# LED_Control_A0-A3.net
KiCad netlist of a schematic drawn in Altium Designer
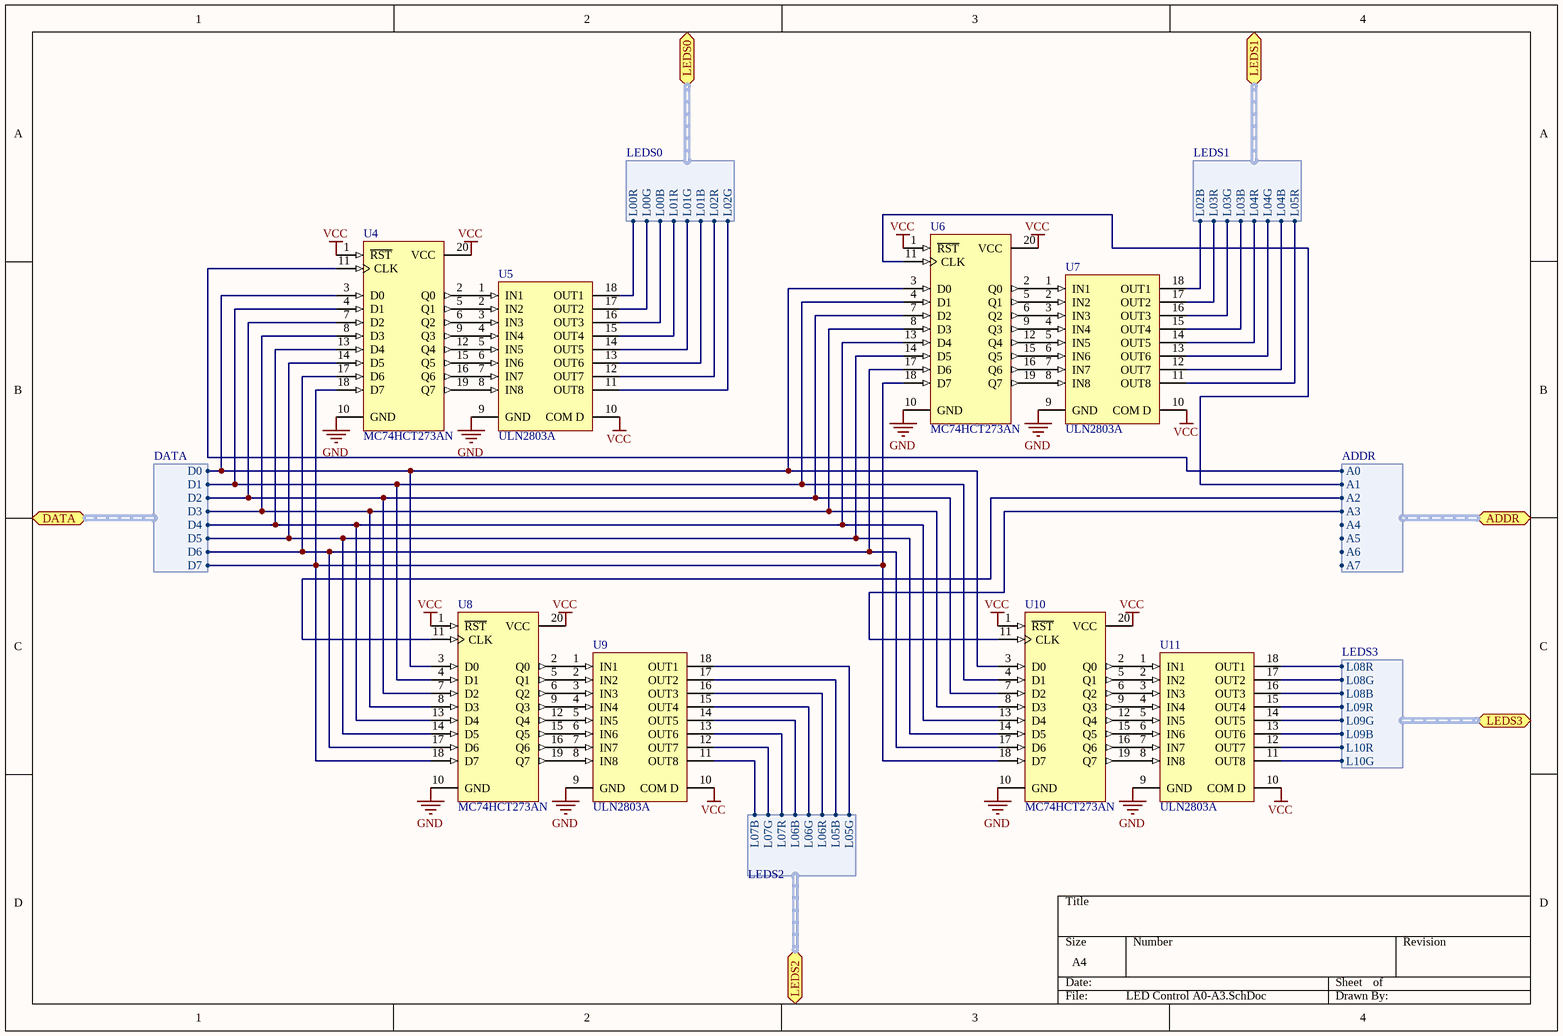
[diagram p0: LED Control A0-A3.SchDoc]

(export (version "E")
  (design (tool "Eeschema 10.0.6"))
  (components
    (comp (ref "U4")
      (value "MC74HCT273AN")
      (footprint "738-03")
      (description "Octal D-Type Flip-Flop with Common Clock and Reset with LSTTL-Compatible Inputs")
      (fields (field (name "PUBLISHER") "Altium Limited"))
      (libsource (lib "ON Semi Logic Flip-Flop") (part "MC74HCT273AN"))
    )
    (comp (ref "U5")
      (value "ULN2803A")
      (footprint "DIP18")
      (description "Eight Darlington Array")
      (fields (field (name "PUBLISHER") "Altium Limited"))
      (libsource (lib "ST Interface Darlington Driver") (part "ULN2803A"))
    )
    (comp (ref "U6")
      (value "MC74HCT273AN")
      (footprint "738-03")
      (description "Octal D-Type Flip-Flop with Common Clock and Reset with LSTTL-Compatible Inputs")
      (fields (field (name "PUBLISHER") "Altium Limited"))
      (libsource (lib "ON Semi Logic Flip-Flop") (part "MC74HCT273AN"))
    )
    (comp (ref "U7")
      (value "ULN2803A")
      (footprint "DIP18")
      (description "Eight Darlington Array")
      (fields (field (name "PUBLISHER") "Altium Limited"))
      (libsource (lib "ST Interface Darlington Driver") (part "ULN2803A"))
    )
    (comp (ref "U8")
      (value "MC74HCT273AN")
      (footprint "738-03")
      (description "Octal D-Type Flip-Flop with Common Clock and Reset with LSTTL-Compatible Inputs")
      (fields (field (name "PUBLISHER") "Altium Limited"))
      (libsource (lib "ON Semi Logic Flip-Flop") (part "MC74HCT273AN"))
    )
    (comp (ref "U9")
      (value "ULN2803A")
      (footprint "DIP18")
      (description "Eight Darlington Array")
      (fields (field (name "PUBLISHER") "Altium Limited"))
      (libsource (lib "ST Interface Darlington Driver") (part "ULN2803A"))
    )
    (comp (ref "U10")
      (value "MC74HCT273AN")
      (footprint "738-03")
      (description "Octal D-Type Flip-Flop with Common Clock and Reset with LSTTL-Compatible Inputs")
      (fields (field (name "PUBLISHER") "Altium Limited"))
      (libsource (lib "ON Semi Logic Flip-Flop") (part "MC74HCT273AN"))
    )
    (comp (ref "U11")
      (value "ULN2803A")
      (footprint "DIP18")
      (description "Eight Darlington Array")
      (fields (field (name "PUBLISHER") "Altium Limited"))
      (libsource (lib "ST Interface Darlington Driver") (part "ULN2803A"))
    )
  )
  (nets
    (net (code "7") (name "/A0") (class "Default")
      (node (ref "U4") (pin "11") (pinfunction "CLK_11") (pintype "input"))
    )
    (net (code "8") (name "/A1") (class "Default")
      (node (ref "U6") (pin "11") (pinfunction "CLK_11") (pintype "input"))
    )
    (net (code "9") (name "/A2") (class "Default")
      (node (ref "U8") (pin "11") (pinfunction "CLK_11") (pintype "input"))
    )
    (net (code "10") (name "/A3") (class "Default")
      (node (ref "U10") (pin "11") (pinfunction "CLK_11") (pintype "input"))
    )
    (net (code "11") (name "/D0") (class "Default")
      (node (ref "U10") (pin "3") (pinfunction "D0_3") (pintype "input"))
      (node (ref "U4") (pin "3") (pinfunction "D0_3") (pintype "input"))
      (node (ref "U6") (pin "3") (pinfunction "D0_3") (pintype "input"))
      (node (ref "U8") (pin "3") (pinfunction "D0_3") (pintype "input"))
    )
    (net (code "12") (name "/D1") (class "Default")
      (node (ref "U10") (pin "4") (pinfunction "D1_4") (pintype "input"))
      (node (ref "U4") (pin "4") (pinfunction "D1_4") (pintype "input"))
      (node (ref "U6") (pin "4") (pinfunction "D1_4") (pintype "input"))
      (node (ref "U8") (pin "4") (pinfunction "D1_4") (pintype "input"))
    )
    (net (code "13") (name "/D2") (class "Default")
      (node (ref "U10") (pin "7") (pinfunction "D2_7") (pintype "input"))
      (node (ref "U4") (pin "7") (pinfunction "D2_7") (pintype "input"))
      (node (ref "U6") (pin "7") (pinfunction "D2_7") (pintype "input"))
      (node (ref "U8") (pin "7") (pinfunction "D2_7") (pintype "input"))
    )
    (net (code "14") (name "/D3") (class "Default")
      (node (ref "U10") (pin "8") (pinfunction "D3_8") (pintype "input"))
      (node (ref "U4") (pin "8") (pinfunction "D3_8") (pintype "input"))
      (node (ref "U6") (pin "8") (pinfunction "D3_8") (pintype "input"))
      (node (ref "U8") (pin "8") (pinfunction "D3_8") (pintype "input"))
    )
    (net (code "15") (name "/D4") (class "Default")
      (node (ref "U10") (pin "13") (pinfunction "D4_13") (pintype "input"))
      (node (ref "U4") (pin "13") (pinfunction "D4_13") (pintype "input"))
      (node (ref "U6") (pin "13") (pinfunction "D4_13") (pintype "input"))
      (node (ref "U8") (pin "13") (pinfunction "D4_13") (pintype "input"))
    )
    (net (code "16") (name "/D5") (class "Default")
      (node (ref "U10") (pin "14") (pinfunction "D5_14") (pintype "input"))
      (node (ref "U4") (pin "14") (pinfunction "D5_14") (pintype "input"))
      (node (ref "U6") (pin "14") (pinfunction "D5_14") (pintype "input"))
      (node (ref "U8") (pin "14") (pinfunction "D5_14") (pintype "input"))
    )
    (net (code "17") (name "/D6") (class "Default")
      (node (ref "U10") (pin "17") (pinfunction "D6_17") (pintype "input"))
      (node (ref "U4") (pin "17") (pinfunction "D6_17") (pintype "input"))
      (node (ref "U6") (pin "17") (pinfunction "D6_17") (pintype "input"))
      (node (ref "U8") (pin "17") (pinfunction "D6_17") (pintype "input"))
    )
    (net (code "18") (name "/D7") (class "Default")
      (node (ref "U10") (pin "18") (pinfunction "D7_18") (pintype "input"))
      (node (ref "U4") (pin "18") (pinfunction "D7_18") (pintype "input"))
      (node (ref "U6") (pin "18") (pinfunction "D7_18") (pintype "input"))
      (node (ref "U8") (pin "18") (pinfunction "D7_18") (pintype "input"))
    )
    (net (code "19") (name "/L00B") (class "Default")
      (node (ref "U5") (pin "16") (pinfunction "OUT3_16") (pintype "open_collector"))
    )
    (net (code "20") (name "/L00G") (class "Default")
      (node (ref "U5") (pin "17") (pinfunction "OUT2_17") (pintype "open_collector"))
    )
    (net (code "21") (name "/L00R") (class "Default")
      (node (ref "U5") (pin "18") (pinfunction "OUT1_18") (pintype "open_collector"))
    )
    (net (code "22") (name "/L01B") (class "Default")
      (node (ref "U5") (pin "13") (pinfunction "OUT6_13") (pintype "open_collector"))
    )
    (net (code "23") (name "/L01G") (class "Default")
      (node (ref "U5") (pin "14") (pinfunction "OUT5_14") (pintype "open_collector"))
    )
    (net (code "24") (name "/L01R") (class "Default")
      (node (ref "U5") (pin "15") (pinfunction "OUT4_15") (pintype "open_collector"))
    )
    (net (code "25") (name "/L02B") (class "Default")
      (node (ref "U7") (pin "18") (pinfunction "OUT1_18") (pintype "open_collector"))
    )
    (net (code "26") (name "/L02G") (class "Default")
      (node (ref "U5") (pin "11") (pinfunction "OUT8_11") (pintype "open_collector"))
    )
    (net (code "27") (name "/L02R") (class "Default")
      (node (ref "U5") (pin "12") (pinfunction "OUT7_12") (pintype "open_collector"))
    )
    (net (code "28") (name "/L03B") (class "Default")
      (node (ref "U7") (pin "15") (pinfunction "OUT4_15") (pintype "open_collector"))
    )
    (net (code "29") (name "/L03G") (class "Default")
      (node (ref "U7") (pin "16") (pinfunction "OUT3_16") (pintype "open_collector"))
    )
    (net (code "30") (name "/L03R") (class "Default")
      (node (ref "U7") (pin "17") (pinfunction "OUT2_17") (pintype "open_collector"))
    )
    (net (code "31") (name "/L04B") (class "Default")
      (node (ref "U7") (pin "12") (pinfunction "OUT7_12") (pintype "open_collector"))
    )
    (net (code "32") (name "/L04G") (class "Default")
      (node (ref "U7") (pin "13") (pinfunction "OUT6_13") (pintype "open_collector"))
    )
    (net (code "33") (name "/L04R") (class "Default")
      (node (ref "U7") (pin "14") (pinfunction "OUT5_14") (pintype "open_collector"))
    )
    (net (code "34") (name "/L05B") (class "Default")
      (node (ref "U9") (pin "17") (pinfunction "OUT2_17") (pintype "open_collector"))
    )
    (net (code "35") (name "/L05G") (class "Default")
      (node (ref "U9") (pin "18") (pinfunction "OUT1_18") (pintype "open_collector"))
    )
    (net (code "36") (name "/L05R") (class "Default")
      (node (ref "U7") (pin "11") (pinfunction "OUT8_11") (pintype "open_collector"))
    )
    (net (code "37") (name "/L06B") (class "Default")
      (node (ref "U9") (pin "14") (pinfunction "OUT5_14") (pintype "open_collector"))
    )
    (net (code "38") (name "/L06G") (class "Default")
      (node (ref "U9") (pin "15") (pinfunction "OUT4_15") (pintype "open_collector"))
    )
    (net (code "39") (name "/L06R") (class "Default")
      (node (ref "U9") (pin "16") (pinfunction "OUT3_16") (pintype "open_collector"))
    )
    (net (code "40") (name "/L07B") (class "Default")
      (node (ref "U9") (pin "11") (pinfunction "OUT8_11") (pintype "open_collector"))
    )
    (net (code "41") (name "/L07G") (class "Default")
      (node (ref "U9") (pin "12") (pinfunction "OUT7_12") (pintype "open_collector"))
    )
    (net (code "42") (name "/L07R") (class "Default")
      (node (ref "U9") (pin "13") (pinfunction "OUT6_13") (pintype "open_collector"))
    )
    (net (code "43") (name "/L08B") (class "Default")
      (node (ref "U11") (pin "16") (pinfunction "OUT3_16") (pintype "open_collector"))
    )
    (net (code "44") (name "/L08G") (class "Default")
      (node (ref "U11") (pin "17") (pinfunction "OUT2_17") (pintype "open_collector"))
    )
    (net (code "45") (name "/L08R") (class "Default")
      (node (ref "U11") (pin "18") (pinfunction "OUT1_18") (pintype "open_collector"))
    )
    (net (code "46") (name "/L09B") (class "Default")
      (node (ref "U11") (pin "13") (pinfunction "OUT6_13") (pintype "open_collector"))
    )
    (net (code "47") (name "/L09G") (class "Default")
      (node (ref "U11") (pin "14") (pinfunction "OUT5_14") (pintype "open_collector"))
    )
    (net (code "48") (name "/L09R") (class "Default")
      (node (ref "U11") (pin "15") (pinfunction "OUT4_15") (pintype "open_collector"))
    )
    (net (code "49") (name "/L10G") (class "Default")
      (node (ref "U11") (pin "11") (pinfunction "OUT8_11") (pintype "open_collector"))
    )
    (net (code "50") (name "/L10R") (class "Default")
      (node (ref "U11") (pin "12") (pinfunction "OUT7_12") (pintype "open_collector"))
    )
    (net (code "57") (name "GND") (class "Default")
      (node (ref "U10") (pin "10") (pinfunction "GND_10") (pintype "power_in"))
      (node (ref "U11") (pin "9") (pinfunction "GND_9") (pintype "power_in"))
      (node (ref "U4") (pin "10") (pinfunction "GND_10") (pintype "power_in"))
      (node (ref "U5") (pin "9") (pinfunction "GND_9") (pintype "power_in"))
      (node (ref "U6") (pin "10") (pinfunction "GND_10") (pintype "power_in"))
      (node (ref "U7") (pin "9") (pinfunction "GND_9") (pintype "power_in"))
      (node (ref "U8") (pin "10") (pinfunction "GND_10") (pintype "power_in"))
      (node (ref "U9") (pin "9") (pinfunction "GND_9") (pintype "power_in"))
    )
    (net (code "58") (name "Net-(U4-Q0)") (class "Default")
      (node (ref "U4") (pin "2") (pinfunction "Q0_2") (pintype "output"))
      (node (ref "U5") (pin "1") (pinfunction "IN1_1") (pintype "input"))
    )
    (net (code "59") (name "Net-(U4-Q1)") (class "Default")
      (node (ref "U4") (pin "5") (pinfunction "Q1_5") (pintype "output"))
      (node (ref "U5") (pin "2") (pinfunction "IN2_2") (pintype "input"))
    )
    (net (code "60") (name "Net-(U4-Q2)") (class "Default")
      (node (ref "U4") (pin "6") (pinfunction "Q2_6") (pintype "output"))
      (node (ref "U5") (pin "3") (pinfunction "IN3_3") (pintype "input"))
    )
    (net (code "61") (name "Net-(U4-Q3)") (class "Default")
      (node (ref "U4") (pin "9") (pinfunction "Q3_9") (pintype "output"))
      (node (ref "U5") (pin "4") (pinfunction "IN4_4") (pintype "input"))
    )
    (net (code "62") (name "Net-(U4-Q4)") (class "Default")
      (node (ref "U4") (pin "12") (pinfunction "Q4_12") (pintype "output"))
      (node (ref "U5") (pin "5") (pinfunction "IN5_5") (pintype "input"))
    )
    (net (code "63") (name "Net-(U4-Q5)") (class "Default")
      (node (ref "U4") (pin "15") (pinfunction "Q5_15") (pintype "output"))
      (node (ref "U5") (pin "6") (pinfunction "IN6_6") (pintype "input"))
    )
    (net (code "64") (name "Net-(U4-Q6)") (class "Default")
      (node (ref "U4") (pin "16") (pinfunction "Q6_16") (pintype "output"))
      (node (ref "U5") (pin "7") (pinfunction "IN7_7") (pintype "input"))
    )
    (net (code "65") (name "Net-(U4-Q7)") (class "Default")
      (node (ref "U4") (pin "19") (pinfunction "Q7_19") (pintype "output"))
      (node (ref "U5") (pin "8") (pinfunction "IN8_8") (pintype "input"))
    )
    (net (code "66") (name "Net-(U6-Q0)") (class "Default")
      (node (ref "U6") (pin "2") (pinfunction "Q0_2") (pintype "output"))
      (node (ref "U7") (pin "1") (pinfunction "IN1_1") (pintype "input"))
    )
    (net (code "67") (name "Net-(U6-Q1)") (class "Default")
      (node (ref "U6") (pin "5") (pinfunction "Q1_5") (pintype "output"))
      (node (ref "U7") (pin "2") (pinfunction "IN2_2") (pintype "input"))
    )
    (net (code "68") (name "Net-(U6-Q2)") (class "Default")
      (node (ref "U6") (pin "6") (pinfunction "Q2_6") (pintype "output"))
      (node (ref "U7") (pin "3") (pinfunction "IN3_3") (pintype "input"))
    )
    (net (code "69") (name "Net-(U6-Q3)") (class "Default")
      (node (ref "U6") (pin "9") (pinfunction "Q3_9") (pintype "output"))
      (node (ref "U7") (pin "4") (pinfunction "IN4_4") (pintype "input"))
    )
    (net (code "70") (name "Net-(U6-Q4)") (class "Default")
      (node (ref "U6") (pin "12") (pinfunction "Q4_12") (pintype "output"))
      (node (ref "U7") (pin "5") (pinfunction "IN5_5") (pintype "input"))
    )
    (net (code "71") (name "Net-(U6-Q5)") (class "Default")
      (node (ref "U6") (pin "15") (pinfunction "Q5_15") (pintype "output"))
      (node (ref "U7") (pin "6") (pinfunction "IN6_6") (pintype "input"))
    )
    (net (code "72") (name "Net-(U6-Q6)") (class "Default")
      (node (ref "U6") (pin "16") (pinfunction "Q6_16") (pintype "output"))
      (node (ref "U7") (pin "7") (pinfunction "IN7_7") (pintype "input"))
    )
    (net (code "73") (name "Net-(U6-Q7)") (class "Default")
      (node (ref "U6") (pin "19") (pinfunction "Q7_19") (pintype "output"))
      (node (ref "U7") (pin "8") (pinfunction "IN8_8") (pintype "input"))
    )
    (net (code "74") (name "Net-(U8-Q0)") (class "Default")
      (node (ref "U8") (pin "2") (pinfunction "Q0_2") (pintype "output"))
      (node (ref "U9") (pin "1") (pinfunction "IN1_1") (pintype "input"))
    )
    (net (code "75") (name "Net-(U8-Q1)") (class "Default")
      (node (ref "U8") (pin "5") (pinfunction "Q1_5") (pintype "output"))
      (node (ref "U9") (pin "2") (pinfunction "IN2_2") (pintype "input"))
    )
    (net (code "76") (name "Net-(U8-Q2)") (class "Default")
      (node (ref "U8") (pin "6") (pinfunction "Q2_6") (pintype "output"))
      (node (ref "U9") (pin "3") (pinfunction "IN3_3") (pintype "input"))
    )
    (net (code "77") (name "Net-(U8-Q3)") (class "Default")
      (node (ref "U8") (pin "9") (pinfunction "Q3_9") (pintype "output"))
      (node (ref "U9") (pin "4") (pinfunction "IN4_4") (pintype "input"))
    )
    (net (code "78") (name "Net-(U8-Q4)") (class "Default")
      (node (ref "U8") (pin "12") (pinfunction "Q4_12") (pintype "output"))
      (node (ref "U9") (pin "5") (pinfunction "IN5_5") (pintype "input"))
    )
    (net (code "79") (name "Net-(U8-Q5)") (class "Default")
      (node (ref "U8") (pin "15") (pinfunction "Q5_15") (pintype "output"))
      (node (ref "U9") (pin "6") (pinfunction "IN6_6") (pintype "input"))
    )
    (net (code "80") (name "Net-(U8-Q6)") (class "Default")
      (node (ref "U8") (pin "16") (pinfunction "Q6_16") (pintype "output"))
      (node (ref "U9") (pin "7") (pinfunction "IN7_7") (pintype "input"))
    )
    (net (code "81") (name "Net-(U8-Q7)") (class "Default")
      (node (ref "U8") (pin "19") (pinfunction "Q7_19") (pintype "output"))
      (node (ref "U9") (pin "8") (pinfunction "IN8_8") (pintype "input"))
    )
    (net (code "82") (name "Net-(U10-Q0)") (class "Default")
      (node (ref "U10") (pin "2") (pinfunction "Q0_2") (pintype "output"))
      (node (ref "U11") (pin "1") (pinfunction "IN1_1") (pintype "input"))
    )
    (net (code "83") (name "Net-(U10-Q1)") (class "Default")
      (node (ref "U10") (pin "5") (pinfunction "Q1_5") (pintype "output"))
      (node (ref "U11") (pin "2") (pinfunction "IN2_2") (pintype "input"))
    )
    (net (code "84") (name "Net-(U10-Q2)") (class "Default")
      (node (ref "U10") (pin "6") (pinfunction "Q2_6") (pintype "output"))
      (node (ref "U11") (pin "3") (pinfunction "IN3_3") (pintype "input"))
    )
    (net (code "85") (name "Net-(U10-Q3)") (class "Default")
      (node (ref "U10") (pin "9") (pinfunction "Q3_9") (pintype "output"))
      (node (ref "U11") (pin "4") (pinfunction "IN4_4") (pintype "input"))
    )
    (net (code "86") (name "Net-(U10-Q4)") (class "Default")
      (node (ref "U10") (pin "12") (pinfunction "Q4_12") (pintype "output"))
      (node (ref "U11") (pin "5") (pinfunction "IN5_5") (pintype "input"))
    )
    (net (code "87") (name "Net-(U10-Q5)") (class "Default")
      (node (ref "U10") (pin "15") (pinfunction "Q5_15") (pintype "output"))
      (node (ref "U11") (pin "6") (pinfunction "IN6_6") (pintype "input"))
    )
    (net (code "88") (name "Net-(U10-Q6)") (class "Default")
      (node (ref "U10") (pin "16") (pinfunction "Q6_16") (pintype "output"))
      (node (ref "U11") (pin "7") (pinfunction "IN7_7") (pintype "input"))
    )
    (net (code "89") (name "Net-(U10-Q7)") (class "Default")
      (node (ref "U10") (pin "19") (pinfunction "Q7_19") (pintype "output"))
      (node (ref "U11") (pin "8") (pinfunction "IN8_8") (pintype "input"))
    )
    (net (code "90") (name "VCC") (class "Default")
      (node (ref "U10") (pin "1") (pinfunction "~{RST}_1") (pintype "input"))
      (node (ref "U10") (pin "20") (pinfunction "VCC_20") (pintype "power_in"))
      (node (ref "U11") (pin "10") (pinfunction "COM_D_10") (pintype "passive"))
      (node (ref "U4") (pin "1") (pinfunction "~{RST}_1") (pintype "input"))
      (node (ref "U4") (pin "20") (pinfunction "VCC_20") (pintype "power_in"))
      (node (ref "U5") (pin "10") (pinfunction "COM_D_10") (pintype "passive"))
      (node (ref "U6") (pin "1") (pinfunction "~{RST}_1") (pintype "input"))
      (node (ref "U6") (pin "20") (pinfunction "VCC_20") (pintype "power_in"))
      (node (ref "U7") (pin "10") (pinfunction "COM_D_10") (pintype "passive"))
      (node (ref "U8") (pin "1") (pinfunction "~{RST}_1") (pintype "input"))
      (node (ref "U8") (pin "20") (pinfunction "VCC_20") (pintype "power_in"))
      (node (ref "U9") (pin "10") (pinfunction "COM_D_10") (pintype "passive"))
    )
  )
)
